# targetboard.net
KiCad netlist of a schematic drawn in EAGLE
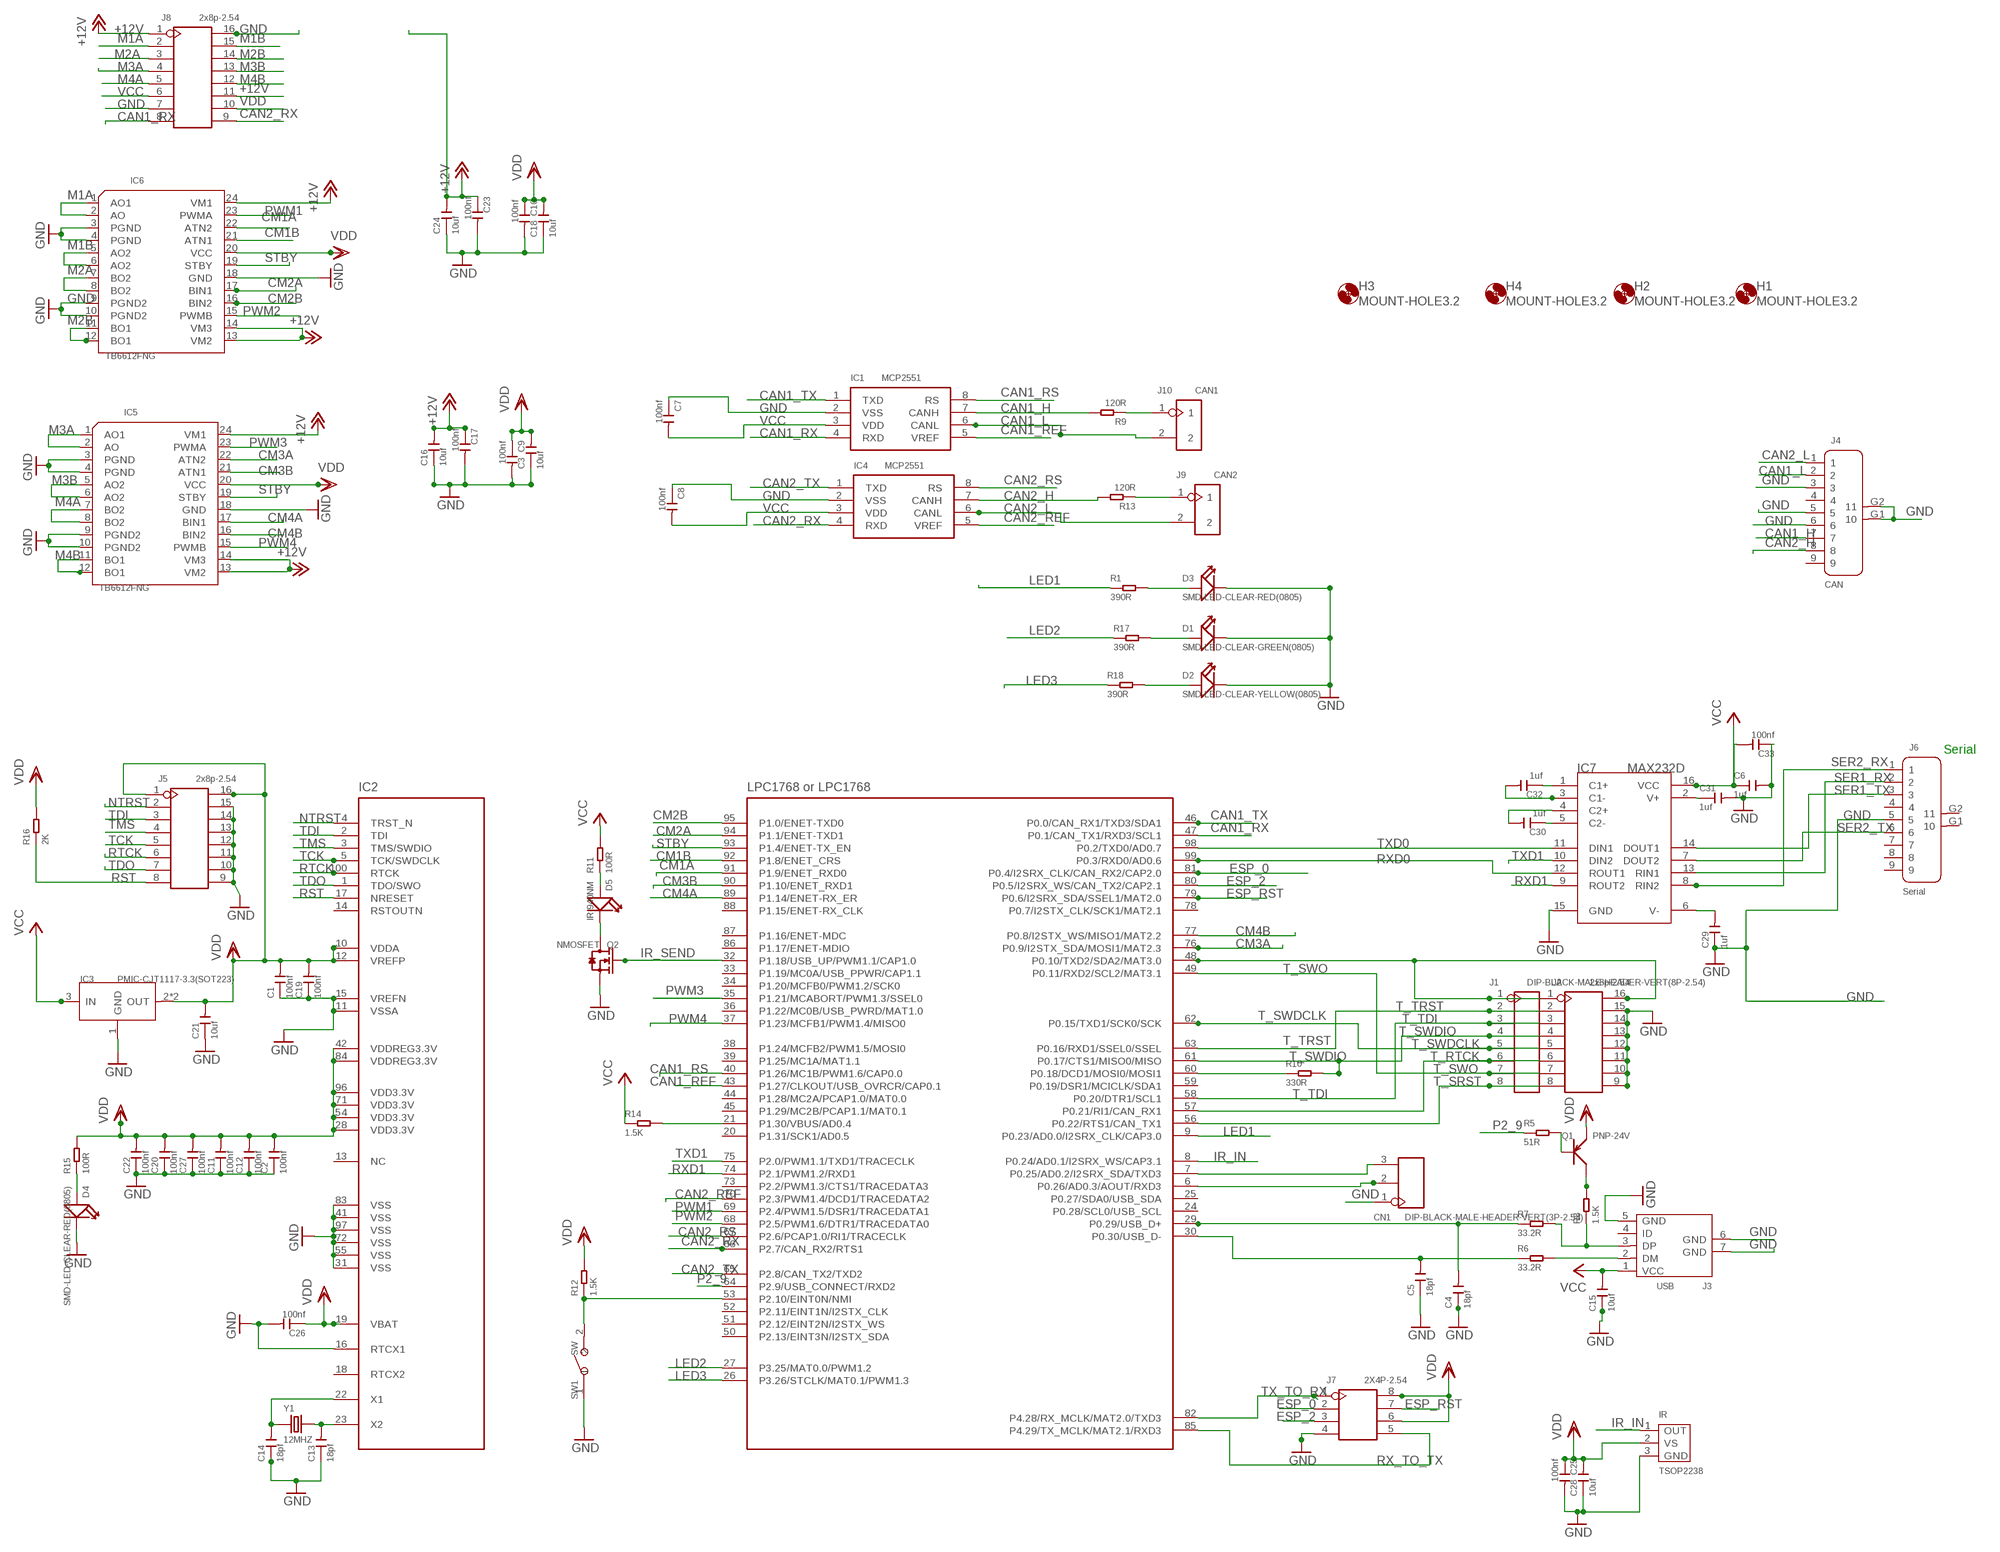
[diagram p0: schematic, sheet 1]

(export (version "E")
  (design (tool "Eeschema 10.0.6"))
  (components
    (comp (ref "C1")
      (value "100nf")
      (footprint "eagle-import:C0805")
      (fields (field (name "MPN") "CC0805KRX7R9BB104"))
      (libsource (lib "eagle-import") (part "CERAMIC-100NF-50V-10%-X7R(0805)"))
    )
    (comp (ref "C2")
      (value "100nf")
      (footprint "eagle-import:C0805")
      (fields (field (name "MPN") "CC0805KRX7R9BB104"))
      (libsource (lib "eagle-import") (part "CERAMIC-100NF-50V-10%-X7R(0805)"))
    )
    (comp (ref "C3")
      (value "10uf")
      (footprint "eagle-import:C0805")
      (fields (field (name "MPN") "CC0805KKX5R8BB106"))
      (libsource (lib "eagle-import") (part "CERAMIC-10UF-25V-10%-X5R(0805)"))
    )
    (comp (ref "C4")
      (value "18pf")
      (footprint "eagle-import:C0805")
      (libsource (lib "eagle-import") (part "CERAMIC-18PF-50V-5%-NPO(0805)"))
    )
    (comp (ref "C5")
      (value "18pf")
      (footprint "eagle-import:C0805")
      (libsource (lib "eagle-import") (part "CERAMIC-18PF-50V-5%-NPO(0805)"))
    )
    (comp (ref "C6")
      (value "1uf")
      (footprint "eagle-import:C0805")
      (fields (field (name "MPN") "CC0805KKX7R8BB105"))
      (libsource (lib "eagle-import") (part "CERAMIC-1UF-25V-10%-X7R(0805)"))
    )
    (comp (ref "C7")
      (value "100nf")
      (footprint "eagle-import:C0805")
      (fields (field (name "MPN") "CC0805KRX7R9BB104"))
      (libsource (lib "eagle-import") (part "CERAMIC-100NF-50V-10%-X7R(0805)"))
    )
    (comp (ref "C8")
      (value "100nf")
      (footprint "eagle-import:C0805")
      (fields (field (name "MPN") "CC0805KRX7R9BB104"))
      (libsource (lib "eagle-import") (part "CERAMIC-100NF-50V-10%-X7R(0805)"))
    )
    (comp (ref "C9")
      (value "100nf")
      (footprint "eagle-import:C0805")
      (fields (field (name "MPN") "CC0805KRX7R9BB104"))
      (libsource (lib "eagle-import") (part "CERAMIC-100NF-50V-10%-X7R(0805)"))
    )
    (comp (ref "C10")
      (value "100nf")
      (footprint "eagle-import:C0805")
      (fields (field (name "MPN") "CC0805KRX7R9BB104"))
      (libsource (lib "eagle-import") (part "CERAMIC-100NF-50V-10%-X7R(0805)"))
    )
    (comp (ref "C11")
      (value "100nf")
      (footprint "eagle-import:C0805")
      (fields (field (name "MPN") "CC0805KRX7R9BB104"))
      (libsource (lib "eagle-import") (part "CERAMIC-100NF-50V-10%-X7R(0805)"))
    )
    (comp (ref "C12")
      (value "100nf")
      (footprint "eagle-import:C0805")
      (fields (field (name "MPN") "CC0805KRX7R9BB104"))
      (libsource (lib "eagle-import") (part "CERAMIC-100NF-50V-10%-X7R(0805)"))
    )
    (comp (ref "C13")
      (value "18pf")
      (footprint "eagle-import:C0805")
      (libsource (lib "eagle-import") (part "CERAMIC-18PF-50V-5%-NPO(0805)"))
    )
    (comp (ref "C14")
      (value "18pf")
      (footprint "eagle-import:C0805")
      (libsource (lib "eagle-import") (part "CERAMIC-18PF-50V-5%-NPO(0805)"))
    )
    (comp (ref "C15")
      (value "10uf")
      (footprint "eagle-import:C0603")
      (fields (field (name "MPN") "CC0603KRX5R6BB106"))
      (libsource (lib "eagle-import") (part "CERAMIC-10UF-10V-10%-X5R(0603)"))
    )
    (comp (ref "C16")
      (value "10uf")
      (footprint "eagle-import:C0805")
      (fields (field (name "MPN") "CC0805KKX5R8BB106"))
      (libsource (lib "eagle-import") (part "CERAMIC-10UF-25V-10%-X5R(0805)"))
    )
    (comp (ref "C17")
      (value "100nf")
      (footprint "eagle-import:C0805")
      (fields (field (name "MPN") "CC0805KRX7R9BB104"))
      (libsource (lib "eagle-import") (part "CERAMIC-100NF-50V-10%-X7R(0805)"))
    )
    (comp (ref "C18")
      (value "10uf")
      (footprint "eagle-import:C0805")
      (fields (field (name "MPN") "CC0805KKX5R8BB106"))
      (libsource (lib "eagle-import") (part "CERAMIC-10UF-25V-10%-X5R(0805)"))
    )
    (comp (ref "C19")
      (value "100nf")
      (footprint "eagle-import:C0805")
      (fields (field (name "MPN") "CC0805KRX7R9BB104"))
      (libsource (lib "eagle-import") (part "CERAMIC-100NF-50V-10%-X7R(0805)"))
    )
    (comp (ref "C20")
      (value "100nf")
      (footprint "eagle-import:C0805")
      (fields (field (name "MPN") "CC0805KRX7R9BB104"))
      (libsource (lib "eagle-import") (part "CERAMIC-100NF-50V-10%-X7R(0805)"))
    )
    (comp (ref "C21")
      (value "10uf")
      (footprint "eagle-import:C0805")
      (fields (field (name "MPN") "CC0805KKX5R8BB106"))
      (libsource (lib "eagle-import") (part "CERAMIC-10UF-25V-10%-X5R(0805)"))
    )
    (comp (ref "C22")
      (value "100nf")
      (footprint "eagle-import:C0805")
      (fields (field (name "MPN") "CC0805KRX7R9BB104"))
      (libsource (lib "eagle-import") (part "CERAMIC-100NF-50V-10%-X7R(0805)"))
    )
    (comp (ref "C23")
      (value "100nf")
      (footprint "eagle-import:C0805")
      (fields (field (name "MPN") "CC0805KRX7R9BB104"))
      (libsource (lib "eagle-import") (part "CERAMIC-100NF-50V-10%-X7R(0805)"))
    )
    (comp (ref "C24")
      (value "10uf")
      (footprint "eagle-import:C0805")
      (fields (field (name "MPN") "CC0805KKX5R8BB106"))
      (libsource (lib "eagle-import") (part "CERAMIC-10UF-25V-10%-X5R(0805)"))
    )
    (comp (ref "C25")
      (value "100nf")
      (footprint "eagle-import:C0805")
      (fields (field (name "MPN") "CC0805KRX7R9BB104"))
      (libsource (lib "eagle-import") (part "CERAMIC-100NF-50V-10%-X7R(0805)"))
    )
    (comp (ref "C26")
      (value "100nf")
      (footprint "eagle-import:C0805")
      (fields (field (name "MPN") "CC0805KRX7R9BB104"))
      (libsource (lib "eagle-import") (part "CERAMIC-100NF-50V-10%-X7R(0805)"))
    )
    (comp (ref "C27")
      (value "100nf")
      (footprint "eagle-import:C0805")
      (fields (field (name "MPN") "CC0805KRX7R9BB104"))
      (libsource (lib "eagle-import") (part "CERAMIC-100NF-50V-10%-X7R(0805)"))
    )
    (comp (ref "C28")
      (value "10uf")
      (footprint "eagle-import:C0805")
      (fields (field (name "MPN") "CC0805KKX5R8BB106"))
      (libsource (lib "eagle-import") (part "CERAMIC-10UF-25V-10%-X5R(0805)"))
    )
    (comp (ref "C29")
      (value "1uf")
      (footprint "eagle-import:C0805")
      (fields (field (name "MPN") "CC0805KKX7R8BB105"))
      (libsource (lib "eagle-import") (part "CERAMIC-1UF-25V-10%-X7R(0805)"))
    )
    (comp (ref "C30")
      (value "1uf")
      (footprint "eagle-import:C0805")
      (fields (field (name "MPN") "CC0805KKX7R8BB105"))
      (libsource (lib "eagle-import") (part "CERAMIC-1UF-25V-10%-X7R(0805)"))
    )
    (comp (ref "C31")
      (value "1uf")
      (footprint "eagle-import:C0805")
      (fields (field (name "MPN") "CC0805KKX7R8BB105"))
      (libsource (lib "eagle-import") (part "CERAMIC-1UF-25V-10%-X7R(0805)"))
    )
    (comp (ref "C32")
      (value "1uf")
      (footprint "eagle-import:C0805")
      (fields (field (name "MPN") "CC0805KKX7R8BB105"))
      (libsource (lib "eagle-import") (part "CERAMIC-1UF-25V-10%-X7R(0805)"))
    )
    (comp (ref "C33")
      (value "100nf")
      (footprint "eagle-import:C0805")
      (fields (field (name "MPN") "CC0805KRX7R9BB104"))
      (libsource (lib "eagle-import") (part "CERAMIC-100NF-50V-10%-X7R(0805)"))
    )
    (comp (ref "CN1")
      (value "DIP-BLACK-MALE-HEADER-VERT(3P-2.54)")
      (footprint "eagle-import:H3-2.54")
      (libsource (lib "eagle-import") (part "DIP-BLACK-MALE-HEADER-VERT(3P-2.54)"))
    )
    (comp (ref "D1")
      (value "SMD-LED-CLEAR-GREEN(0805)")
      (footprint "eagle-import:LED-0805")
      (fields (field (name "MPN") "17-215SYGC/S530-E2/TR8"))
      (libsource (lib "eagle-import") (part "SMD-LED-CLEAR-GREEN(0805)"))
    )
    (comp (ref "D2")
      (value "SMD-LED-CLEAR-YELLOW(0805)")
      (footprint "eagle-import:LED-0805")
      (fields (field (name "MPN") "17-215UYC/S530-A3/TR8"))
      (libsource (lib "eagle-import") (part "SMD-LED-CLEAR-YELLOW(0805)"))
    )
    (comp (ref "D3")
      (value "SMD-LED-CLEAR-RED(0805)")
      (footprint "eagle-import:LED-0805")
      (fields (field (name "MPN") "17-215SURC/S530-A2/TR8"))
      (libsource (lib "eagle-import") (part "SMD-LED-CLEAR-RED(0805)"))
    )
    (comp (ref "D4")
      (value "SMD-LED-CLEAR-RED(0805)")
      (footprint "eagle-import:LED-0805")
      (fields (field (name "MPN") "17-215SURC/S530-A2/TR8"))
      (libsource (lib "eagle-import") (part "SMD-LED-CLEAR-RED(0805)"))
    )
    (comp (ref "D5")
      (value "IR 940NM")
      (footprint "eagle-import:LED2-2.54-D5.0MM")
      (fields (field (name "MPN") "IR523B-W60W1"))
      (libsource (lib "eagle-import") (part "DIP-IR-LED-940NM(2P-D5MM)"))
    )
    (comp (ref "H1")
      (value "MOUNT-HOLE3.2")
      (footprint "eagle-import:3,2")
      (libsource (lib "eagle-import") (part "MOUNT-HOLE3.2"))
    )
    (comp (ref "H2")
      (value "MOUNT-HOLE3.2")
      (footprint "eagle-import:3,2")
      (libsource (lib "eagle-import") (part "MOUNT-HOLE3.2"))
    )
    (comp (ref "H3")
      (value "MOUNT-HOLE3.2")
      (footprint "eagle-import:3,2")
      (libsource (lib "eagle-import") (part "MOUNT-HOLE3.2"))
    )
    (comp (ref "H4")
      (value "MOUNT-HOLE3.2")
      (footprint "eagle-import:3,2")
      (libsource (lib "eagle-import") (part "MOUNT-HOLE3.2"))
    )
    (comp (ref "IC1")
      (value "MCP2551")
      (footprint "eagle-import:SOIC8-1.27-5X4MM")
      (fields (field (name "MPN") "MCP2551-I/SN"))
      (libsource (lib "eagle-import") (part "INTERFACE-MCP2551-I/SN(SOIC8)"))
    )
    (comp (ref "IC2")
      (value "LPC1768 or LPC1768")
      (footprint "eagle-import:LQFP100-0.5-13.8X13.8MM")
      (fields (field (name "MPN") "LPC1768FBD100"))
      (libsource (lib "eagle-import") (part "MCU_LPC1768FBD100(LQFP100)"))
    )
    (comp (ref "IC3")
      (value "PMIC-CJT1117-3.3(SOT223)")
      (footprint "eagle-import:SOT-223")
      (fields (field (name "MPN") "CJT1117-3.3"))
      (libsource (lib "eagle-import") (part "PMIC-CJT1117-3.3(SOT223)"))
    )
    (comp (ref "IC4")
      (value "MCP2551")
      (footprint "eagle-import:SOIC8-1.27-5X4MM")
      (fields (field (name "MPN") "MCP2551-I/SN"))
      (libsource (lib "eagle-import") (part "INTERFACE-MCP2551-I/SN(SOIC8)"))
    )
    (comp (ref "IC5")
      (value "TB6612FNG")
      (footprint "eagle-import:SSOP24-0.65-8.9X5.3MM")
      (fields (field (name "MPN") "TB6612FNG-O/C8/EL"))
      (libsource (lib "eagle-import") (part "DRIVER-TB6612FNG-O/C8/EL(SSOP24)"))
    )
    (comp (ref "IC6")
      (value "TB6612FNG")
      (footprint "eagle-import:SSOP24-0.65-8.9X5.3MM")
      (fields (field (name "MPN") "TB6612FNG-O/C8/EL"))
      (libsource (lib "eagle-import") (part "DRIVER-TB6612FNG-O/C8/EL(SSOP24)"))
    )
    (comp (ref "IC7")
      (value "MAX232D")
      (footprint "eagle-import:SOIC16-1.27-10X3.9MM")
      (libsource (lib "eagle-import") (part "RECEIVER-MAX232D(SOIC16)"))
    )
    (comp (ref "IR")
      (value "TSOP2238")
      (footprint "eagle-import:SNR3-2.54-6.95X6.0X5.6MM")
      (libsource (lib "eagle-import") (part "OPTICAL-TSOP2238"))
    )
    (comp (ref "J1")
      (value "DIP-BLACK-MALE-HEADER-VERT(8P-2.54)")
      (footprint "eagle-import:H8-2.54")
      (fields (field (name "MPN") "P125-1108A1BS116A1"))
      (libsource (lib "eagle-import") (part "DIP-BLACK-MALE-HEADER-VERT(8P-2.54)"))
    )
    (comp (ref "J2")
      (value "2x8p-2.54")
      (footprint "eagle-import:H2X8-2.54")
      (fields (field (name "MPN") "P125-1216A0AS116A1"))
      (libsource (lib "eagle-import") (part "DIP-BLACK-MALE-HEADER-VERT(2X8P-2.54)"))
    )
    (comp (ref "J3")
      (value "USB")
      (footprint "eagle-import:MICRO-USB5+2P-SMD-0.65")
      (fields (field (name "MPN") "ST-USB-001L"))
      (libsource (lib "eagle-import") (part "MICRO-USB-SMD-TYPE-AB-R/A(ST-USB-001L)"))
    )
    (comp (ref "J4")
      (value "CAN")
      (footprint "eagle-import:DSUB9+2P-2.77-90D-MALE")
      (libsource (lib "eagle-import") (part "DIP-MALE-DB9-CONNECTOR"))
    )
    (comp (ref "J5")
      (value "2x8p-2.54")
      (footprint "eagle-import:H2X8-2.54")
      (fields (field (name "MPN") "P125-1216A0AS116A1"))
      (libsource (lib "eagle-import") (part "DIP-BLACK-MALE-HEADER-VERT(2X8P-2.54)"))
    )
    (comp (ref "J6")
      (value "Serial")
      (footprint "eagle-import:DSUB9+2P-2.77-90D-MALE")
      (libsource (lib "eagle-import") (part "DIP-MALE-DB9-CONNECTOR"))
    )
    (comp (ref "J7")
      (value "2X4P-2.54")
      (footprint "eagle-import:H2X4-2.54")
      (libsource (lib "eagle-import") (part "DIP-BLACK-FEMALE-HEADER(2X4P-2.54)"))
    )
    (comp (ref "J8")
      (value "2x8p-2.54")
      (footprint "eagle-import:H2X8-2.54")
      (fields (field (name "MPN") "P125-1216A0AS116A1"))
      (libsource (lib "eagle-import") (part "DIP-BLACK-MALE-HEADER-VERT(2X8P-2.54)"))
    )
    (comp (ref "J9")
      (value "CAN2")
      (footprint "eagle-import:H2-2.54")
      (fields (field (name "MPN") "P125-1102A0BS116A3"))
      (libsource (lib "eagle-import") (part "DIP-WHITE-MALE-HEADER-VERT(2P-2.54)"))
    )
    (comp (ref "J10")
      (value "CAN1")
      (footprint "eagle-import:H2-2.54")
      (fields (field (name "MPN") "P125-1102A0BS116A3"))
      (libsource (lib "eagle-import") (part "DIP-WHITE-MALE-HEADER-VERT(2P-2.54)"))
    )
    (comp (ref "Q1")
      (value "PNP-24V")
      (footprint "eagle-import:SOT-23")
      (fields (field (name "MPN") "S8550"))
      (libsource (lib "eagle-import") (part "SMD-TRANSISTORS-PNP-25V-500MA(SOT-23)"))
    )
    (comp (ref "Q2")
      (value "NMOSFET")
      (footprint "eagle-import:SOT-23")
      (fields (field (name "MPN") "2N7002,215"))
      (libsource (lib "eagle-import") (part "SMD-MOSFET-N-CH-60V-300MA-LOGIC-LEVEL-FET(SOT-23)"))
    )
    (comp (ref "R1")
      (value "390R")
      (footprint "eagle-import:R0805")
      (fields (field (name "MPN") "RC0805JR-07390RL"))
      (libsource (lib "eagle-import") (part "SMD-RES-390R-5%-1/8W(0805)"))
    )
    (comp (ref "R5")
      (value "51R")
      (footprint "eagle-import:R0603")
      (fields (field (name "MPN") "RC0603FR-0751RL"))
      (libsource (lib "eagle-import") (part "SMD-RES-51R-1%-1/10W(0603)"))
    )
    (comp (ref "R6")
      (value "33.2R")
      (footprint "eagle-import:R0603")
      (fields (field (name "MPN") "RC0603FR-0733R2L"))
      (libsource (lib "eagle-import") (part "SMD-RES-33.2R-1%-1/10W(0603)"))
    )
    (comp (ref "R7")
      (value "33.2R")
      (footprint "eagle-import:R0603")
      (fields (field (name "MPN") "RC0603FR-0733R2L"))
      (libsource (lib "eagle-import") (part "SMD-RES-33.2R-1%-1/10W(0603)"))
    )
    (comp (ref "R8")
      (value "1.5K")
      (footprint "eagle-import:R0805")
      (fields (field (name "MPN") "RC0805FR-071K5L"))
      (libsource (lib "eagle-import") (part "SMD-RES-1.5K-1%-1/8W(0805)"))
    )
    (comp (ref "R9")
      (value "120R")
      (footprint "eagle-import:R0805")
      (fields (field (name "MPN") "RC0805JR-07120RL"))
      (libsource (lib "eagle-import") (part "SMD-RES-120R-5%-1/8W(0805)"))
    )
    (comp (ref "R10")
      (value "330R")
      (footprint "eagle-import:R0603")
      (fields (field (name "MPN") "RC0603FR-07330RL"))
      (libsource (lib "eagle-import") (part "SMD-RES-330R-1%-1/10W(0603)"))
    )
    (comp (ref "R11")
      (value "100R")
      (footprint "eagle-import:R0805")
      (fields (field (name "MPN") "RC0805JR-07100RL"))
      (libsource (lib "eagle-import") (part "SMD-RES-100R-5%-1/8W(0805)"))
    )
    (comp (ref "R12")
      (value "1.5K")
      (footprint "eagle-import:R0805")
      (fields (field (name "MPN") "RC0805FR-071K5L"))
      (libsource (lib "eagle-import") (part "SMD-RES-1.5K-1%-1/8W(0805)"))
    )
    (comp (ref "R13")
      (value "120R")
      (footprint "eagle-import:R0805")
      (fields (field (name "MPN") "RC0805JR-07120RL"))
      (libsource (lib "eagle-import") (part "SMD-RES-120R-5%-1/8W(0805)"))
    )
    (comp (ref "R14")
      (value "1.5K")
      (footprint "eagle-import:R0805")
      (fields (field (name "MPN") "RC0805FR-071K5L"))
      (libsource (lib "eagle-import") (part "SMD-RES-1.5K-1%-1/8W(0805)"))
    )
    (comp (ref "R15")
      (value "100R")
      (footprint "eagle-import:R0805")
      (fields (field (name "MPN") "RC0805JR-07100RL"))
      (libsource (lib "eagle-import") (part "SMD-RES-100R-5%-1/8W(0805)"))
    )
    (comp (ref "R16")
      (value "2K")
      (footprint "eagle-import:R0805")
      (fields (field (name "MPN") "RC0805JR-072KL"))
      (libsource (lib "eagle-import") (part "SMD-RES-2K-5%-1/8W(0805)"))
    )
    (comp (ref "R17")
      (value "390R")
      (footprint "eagle-import:R0805")
      (fields (field (name "MPN") "RC0805JR-07390RL"))
      (libsource (lib "eagle-import") (part "SMD-RES-390R-5%-1/8W(0805)"))
    )
    (comp (ref "R18")
      (value "390R")
      (footprint "eagle-import:R0805")
      (fields (field (name "MPN") "RC0805JR-07390RL"))
      (libsource (lib "eagle-import") (part "SMD-RES-390R-5%-1/8W(0805)"))
    )
    (comp (ref "SW1")
      (value "SW")
      (footprint "eagle-import:SW2-2.6-3.0X2.5X1.2+0.4MM")
      (libsource (lib "eagle-import") (part "SMD-BUTTON(2P-3.0X2.5X1.2+0.4MM)-B3U-1000P-2P-SMD"))
    )
    (comp (ref "Y1")
      (value "12MHZ")
      (footprint "eagle-import:X2-SMD-5.0X3.2X1.3MM")
      (fields (field (name "MPN") "5032/2P"))
      (libsource (lib "eagle-import") (part "SMD-CRYSTAL-12MHZ-20PF-20PPM-40R(2P-5.0X3.2MM)"))
    )
  )
  (nets
    (net (code "1") (name "+12V") (class "Default")
      (node (ref "C16") (pin "2") (pinfunction "2_2") (pintype "passive"))
      (node (ref "C17") (pin "1") (pinfunction "1_1") (pintype "passive"))
      (node (ref "C23") (pin "1") (pinfunction "1_1") (pintype "passive"))
      (node (ref "C24") (pin "2") (pinfunction "2_2") (pintype "passive"))
      (node (ref "IC5") (pin "13") (pinfunction "VM2_13") (pintype "bidirectional"))
      (node (ref "IC5") (pin "14") (pinfunction "VM3_14") (pintype "bidirectional"))
      (node (ref "IC5") (pin "24") (pinfunction "VM1_24") (pintype "bidirectional"))
      (node (ref "IC6") (pin "13") (pinfunction "VM2_13") (pintype "bidirectional"))
      (node (ref "IC6") (pin "14") (pinfunction "VM3_14") (pintype "bidirectional"))
      (node (ref "IC6") (pin "24") (pinfunction "VM1_24") (pintype "bidirectional"))
      (node (ref "J8") (pin "1") (pinfunction "1_1") (pintype "bidirectional"))
      (node (ref "J8") (pin "11") (pinfunction "11_11") (pintype "bidirectional"))
    )
    (net (code "2") (name "/CAN1_H") (class "Default")
      (node (ref "IC1") (pin "7") (pinfunction "CANH_7") (pintype "bidirectional"))
      (node (ref "J4") (pin "7") (pinfunction "7_7") (pintype "bidirectional"))
      (node (ref "R9") (pin "2") (pinfunction "2_2") (pintype "passive"))
    )
    (net (code "3") (name "/CAN1_L") (class "Default")
      (node (ref "IC1") (pin "6") (pinfunction "CANL_6") (pintype "bidirectional"))
      (node (ref "J10") (pin "2") (pinfunction "2_2") (pintype "bidirectional"))
      (node (ref "J4") (pin "2") (pinfunction "2_2") (pintype "bidirectional"))
    )
    (net (code "4") (name "/CAN1_REF") (class "Default")
      (node (ref "IC1") (pin "5") (pinfunction "VREF_5") (pintype "bidirectional"))
      (node (ref "IC2") (pin "43") (pinfunction "P1.27/CLKOUT/USB_OVRCR/CAP0.1_43") (pintype "bidirectional"))
    )
    (net (code "5") (name "/CAN1_RS") (class "Default")
      (node (ref "IC1") (pin "8") (pinfunction "RS_8") (pintype "bidirectional"))
      (node (ref "IC2") (pin "40") (pinfunction "P1.26/MC1B/PWM1.6/CAP0.0_40") (pintype "bidirectional"))
    )
    (net (code "6") (name "/CAN1_RX") (class "Default")
      (node (ref "IC1") (pin "4") (pinfunction "RXD_4") (pintype "bidirectional"))
      (node (ref "IC2") (pin "47") (pinfunction "P0.1/CAN_TX1/RXD3/SCL1_47") (pintype "bidirectional"))
      (node (ref "J8") (pin "8") (pinfunction "8_8") (pintype "bidirectional"))
    )
    (net (code "7") (name "/CAN1_TX") (class "Default")
      (node (ref "IC1") (pin "1") (pinfunction "TXD_1") (pintype "bidirectional"))
      (node (ref "IC2") (pin "46") (pinfunction "P0.0/CAN_RX1/TXD3/SDA1_46") (pintype "bidirectional"))
    )
    (net (code "8") (name "/CAN2_H") (class "Default")
      (node (ref "IC4") (pin "7") (pinfunction "CANH_7") (pintype "bidirectional"))
      (node (ref "J4") (pin "8") (pinfunction "8_8") (pintype "bidirectional"))
      (node (ref "R13") (pin "2") (pinfunction "2_2") (pintype "passive"))
    )
    (net (code "9") (name "/CAN2_L") (class "Default")
      (node (ref "IC4") (pin "6") (pinfunction "CANL_6") (pintype "bidirectional"))
      (node (ref "J4") (pin "1") (pinfunction "1_1") (pintype "bidirectional"))
      (node (ref "J9") (pin "2") (pinfunction "2_2") (pintype "bidirectional"))
    )
    (net (code "10") (name "/CAN2_REF") (class "Default")
      (node (ref "IC2") (pin "70") (pinfunction "P2.3/PWM1.4/DCD1/TRACEDATA2_70") (pintype "bidirectional"))
      (node (ref "IC4") (pin "5") (pinfunction "VREF_5") (pintype "bidirectional"))
    )
    (net (code "11") (name "/CAN2_RS") (class "Default")
      (node (ref "IC2") (pin "67") (pinfunction "P2.6/PCAP1.0/RI1/TRACECLK_67") (pintype "bidirectional"))
      (node (ref "IC4") (pin "8") (pinfunction "RS_8") (pintype "bidirectional"))
    )
    (net (code "12") (name "/CAN2_RX") (class "Default")
      (node (ref "IC2") (pin "66") (pinfunction "P2.7/CAN_RX2/RTS1_66") (pintype "bidirectional"))
      (node (ref "IC4") (pin "4") (pinfunction "RXD_4") (pintype "bidirectional"))
      (node (ref "J8") (pin "9") (pinfunction "9_9") (pintype "bidirectional"))
    )
    (net (code "13") (name "/CAN2_TX") (class "Default")
      (node (ref "IC2") (pin "65") (pinfunction "P2.8/CAN_TX2/TXD2_65") (pintype "bidirectional"))
      (node (ref "IC4") (pin "1") (pinfunction "TXD_1") (pintype "bidirectional"))
    )
    (net (code "14") (name "/CM1A") (class "Default")
      (node (ref "IC2") (pin "91") (pinfunction "P1.9/ENET_RXD0_91") (pintype "bidirectional"))
      (node (ref "IC6") (pin "22") (pinfunction "ATN2_22") (pintype "bidirectional"))
    )
    (net (code "15") (name "/CM1B") (class "Default")
      (node (ref "IC2") (pin "92") (pinfunction "P1.8/ENET_CRS_92") (pintype "bidirectional"))
      (node (ref "IC6") (pin "21") (pinfunction "ATN1_21") (pintype "bidirectional"))
    )
    (net (code "16") (name "/CM2A") (class "Default")
      (node (ref "IC2") (pin "94") (pinfunction "P1.1/ENET-TXD1_94") (pintype "bidirectional"))
      (node (ref "IC6") (pin "17") (pinfunction "BIN1_17") (pintype "bidirectional"))
    )
    (net (code "17") (name "/CM2B") (class "Default")
      (node (ref "IC2") (pin "95") (pinfunction "P1.0/ENET-TXD0_95") (pintype "bidirectional"))
      (node (ref "IC6") (pin "16") (pinfunction "BIN2_16") (pintype "bidirectional"))
    )
    (net (code "18") (name "/CM3A") (class "Default")
      (node (ref "IC2") (pin "76") (pinfunction "P0.9/I2STX_SDA/MOSI1/MAT2.3_76") (pintype "bidirectional"))
      (node (ref "IC5") (pin "22") (pinfunction "ATN2_22") (pintype "bidirectional"))
    )
    (net (code "19") (name "/CM3B") (class "Default")
      (node (ref "IC2") (pin "90") (pinfunction "P1.10/ENET_RXD1_90") (pintype "bidirectional"))
      (node (ref "IC5") (pin "21") (pinfunction "ATN1_21") (pintype "bidirectional"))
    )
    (net (code "20") (name "/CM4A") (class "Default")
      (node (ref "IC2") (pin "89") (pinfunction "P1.14/ENET-RX_ER_89") (pintype "bidirectional"))
      (node (ref "IC5") (pin "17") (pinfunction "BIN1_17") (pintype "bidirectional"))
    )
    (net (code "21") (name "/CM4B") (class "Default")
      (node (ref "IC2") (pin "77") (pinfunction "P0.8/I2STX_WS/MISO1/MAT2.2_77") (pintype "bidirectional"))
      (node (ref "IC5") (pin "16") (pinfunction "BIN2_16") (pintype "bidirectional"))
    )
    (net (code "22") (name "/ESP_0") (class "Default")
      (node (ref "IC2") (pin "81") (pinfunction "P0.4/I2SRX_CLK/CAN_RX2/CAP2.0_81") (pintype "bidirectional"))
      (node (ref "J7") (pin "2") (pinfunction "2_2") (pintype "bidirectional"))
    )
    (net (code "23") (name "/ESP_2") (class "Default")
      (node (ref "IC2") (pin "80") (pinfunction "P0.5/I2SRX_WS/CAN_TX2/CAP2.1_80") (pintype "bidirectional"))
      (node (ref "J7") (pin "3") (pinfunction "3_3") (pintype "bidirectional"))
    )
    (net (code "24") (name "/ESP_RST") (class "Default")
      (node (ref "IC2") (pin "79") (pinfunction "P0.6/I2SRX_SDA/SSEL1/MAT2.0_79") (pintype "bidirectional"))
      (node (ref "J7") (pin "7") (pinfunction "7_7") (pintype "bidirectional"))
    )
    (net (code "25") (name "/IR_IN") (class "Default")
      (node (ref "IC2") (pin "8") (pinfunction "P0.24/AD0.1/I2SRX_WS/CAP3.1_8") (pintype "bidirectional"))
      (node (ref "IR") (pin "1") (pinfunction "OUT_1") (pintype "bidirectional"))
    )
    (net (code "26") (name "/IR_SEND") (class "Default")
      (node (ref "IC2") (pin "32") (pinfunction "P1.18/USB_UP/PWM1.1/CAP1.0_32") (pintype "bidirectional"))
      (node (ref "Q2") (pin "1") (pinfunction "G_1") (pintype "passive"))
    )
    (net (code "27") (name "/LED1") (class "Default")
      (node (ref "IC2") (pin "9") (pinfunction "P0.23/AD0.0/I2SRX_CLK/CAP3.0_9") (pintype "bidirectional"))
      (node (ref "R1") (pin "1") (pinfunction "1_1") (pintype "passive"))
    )
    (net (code "28") (name "/LED2") (class "Default")
      (node (ref "IC2") (pin "27") (pinfunction "P3.25/MAT0.0/PWM1.2_27") (pintype "bidirectional"))
      (node (ref "R17") (pin "1") (pinfunction "1_1") (pintype "passive"))
    )
    (net (code "29") (name "/LED3") (class "Default")
      (node (ref "IC2") (pin "26") (pinfunction "P3.26/STCLK/MAT0.1/PWM1.3_26") (pintype "bidirectional"))
      (node (ref "R18") (pin "1") (pinfunction "1_1") (pintype "passive"))
    )
    (net (code "30") (name "/M1A") (class "Default")
      (node (ref "IC6") (pin "1") (pinfunction "AO1_1") (pintype "bidirectional"))
      (node (ref "IC6") (pin "2") (pinfunction "AO_2") (pintype "bidirectional"))
      (node (ref "J8") (pin "2") (pinfunction "2_2") (pintype "bidirectional"))
    )
    (net (code "31") (name "/M1B") (class "Default")
      (node (ref "IC6") (pin "5") (pinfunction "AO2_5") (pintype "bidirectional"))
      (node (ref "IC6") (pin "6") (pinfunction "AO2_6") (pintype "bidirectional"))
      (node (ref "J8") (pin "15") (pinfunction "15_15") (pintype "bidirectional"))
    )
    (net (code "32") (name "/M2A") (class "Default")
      (node (ref "IC6") (pin "7") (pinfunction "BO2_7") (pintype "bidirectional"))
      (node (ref "IC6") (pin "8") (pinfunction "BO2_8") (pintype "bidirectional"))
      (node (ref "J8") (pin "3") (pinfunction "3_3") (pintype "bidirectional"))
    )
    (net (code "33") (name "/M2B") (class "Default")
      (node (ref "IC6") (pin "11") (pinfunction "BO1_11") (pintype "bidirectional"))
      (node (ref "IC6") (pin "12") (pinfunction "BO1_12") (pintype "bidirectional"))
      (node (ref "J8") (pin "14") (pinfunction "14_14") (pintype "bidirectional"))
    )
    (net (code "34") (name "/M3A") (class "Default")
      (node (ref "IC5") (pin "1") (pinfunction "AO1_1") (pintype "bidirectional"))
      (node (ref "IC5") (pin "2") (pinfunction "AO_2") (pintype "bidirectional"))
      (node (ref "J8") (pin "4") (pinfunction "4_4") (pintype "bidirectional"))
    )
    (net (code "35") (name "/M3B") (class "Default")
      (node (ref "IC5") (pin "5") (pinfunction "AO2_5") (pintype "bidirectional"))
      (node (ref "IC5") (pin "6") (pinfunction "AO2_6") (pintype "bidirectional"))
      (node (ref "J8") (pin "13") (pinfunction "13_13") (pintype "bidirectional"))
    )
    (net (code "36") (name "/M4A") (class "Default")
      (node (ref "IC5") (pin "7") (pinfunction "BO2_7") (pintype "bidirectional"))
      (node (ref "IC5") (pin "8") (pinfunction "BO2_8") (pintype "bidirectional"))
      (node (ref "J8") (pin "5") (pinfunction "5_5") (pintype "bidirectional"))
    )
    (net (code "37") (name "/M4B") (class "Default")
      (node (ref "IC5") (pin "11") (pinfunction "BO1_11") (pintype "bidirectional"))
      (node (ref "IC5") (pin "12") (pinfunction "BO1_12") (pintype "bidirectional"))
      (node (ref "J8") (pin "12") (pinfunction "12_12") (pintype "bidirectional"))
    )
    (net (code "38") (name "/NTRST") (class "Default")
      (node (ref "IC2") (pin "4") (pinfunction "TRST_N_4") (pintype "bidirectional"))
      (node (ref "J5") (pin "2") (pinfunction "2_2") (pintype "bidirectional"))
    )
    (net (code "39") (name "/P2_9") (class "Default")
      (node (ref "IC2") (pin "64") (pinfunction "P2.9/USB_CONNECT/RXD2_64") (pintype "bidirectional"))
      (node (ref "R5") (pin "1") (pinfunction "1_1") (pintype "passive"))
    )
    (net (code "40") (name "/PWM1") (class "Default")
      (node (ref "IC2") (pin "69") (pinfunction "P2.4/PWM1.5/DSR1/TRACEDATA1_69") (pintype "bidirectional"))
      (node (ref "IC6") (pin "23") (pinfunction "PWMA_23") (pintype "bidirectional"))
    )
    (net (code "41") (name "/PWM2") (class "Default")
      (node (ref "IC2") (pin "68") (pinfunction "P2.5/PWM1.6/DTR1/TRACEDATA0_68") (pintype "bidirectional"))
      (node (ref "IC6") (pin "15") (pinfunction "PWMB_15") (pintype "bidirectional"))
    )
    (net (code "42") (name "/PWM3") (class "Default")
      (node (ref "IC2") (pin "35") (pinfunction "P1.21/MCABORT/PWM1.3/SSEL0_35") (pintype "bidirectional"))
      (node (ref "IC5") (pin "23") (pinfunction "PWMA_23") (pintype "bidirectional"))
    )
    (net (code "43") (name "/PWM4") (class "Default")
      (node (ref "IC2") (pin "37") (pinfunction "P1.23/MCFB1/PWM1.4/MISO0_37") (pintype "bidirectional"))
      (node (ref "IC5") (pin "15") (pinfunction "PWMB_15") (pintype "bidirectional"))
    )
    (net (code "44") (name "/RST") (class "Default")
      (node (ref "IC2") (pin "17") (pinfunction "NRESET_17") (pintype "bidirectional"))
      (node (ref "J5") (pin "8") (pinfunction "8_8") (pintype "bidirectional"))
      (node (ref "R16") (pin "1") (pinfunction "1_1") (pintype "passive"))
    )
    (net (code "45") (name "/RTCK") (class "Default")
      (node (ref "IC2") (pin "100") (pinfunction "RTCK_100") (pintype "bidirectional"))
      (node (ref "J5") (pin "6") (pinfunction "6_6") (pintype "bidirectional"))
    )
    (net (code "46") (name "/RXD0") (class "Default")
      (node (ref "IC2") (pin "99") (pinfunction "P0.3/RXD0/AD0.6_99") (pintype "bidirectional"))
      (node (ref "IC7") (pin "12") (pinfunction "ROUT1_12") (pintype "bidirectional"))
    )
    (net (code "47") (name "/RXD1") (class "Default")
      (node (ref "IC2") (pin "74") (pinfunction "P2.1/PWM1.2/RXD1_74") (pintype "bidirectional"))
      (node (ref "IC7") (pin "9") (pinfunction "ROUT2_9") (pintype "bidirectional"))
    )
    (net (code "48") (name "/RX_TO_TX") (class "Default")
      (node (ref "IC2") (pin "85") (pinfunction "P4.29/TX_MCLK/MAT2.1/RXD3_85") (pintype "bidirectional"))
      (node (ref "J7") (pin "5") (pinfunction "5_5") (pintype "bidirectional"))
    )
    (net (code "49") (name "/SER1_RX") (class "Default")
      (node (ref "IC7") (pin "13") (pinfunction "RIN1_13") (pintype "bidirectional"))
      (node (ref "J6") (pin "2") (pinfunction "2_2") (pintype "bidirectional"))
    )
    (net (code "50") (name "/SER1_TX") (class "Default")
      (node (ref "IC7") (pin "14") (pinfunction "DOUT1_14") (pintype "bidirectional"))
      (node (ref "J6") (pin "3") (pinfunction "3_3") (pintype "bidirectional"))
    )
    (net (code "51") (name "/SER2_RX") (class "Default")
      (node (ref "IC7") (pin "8") (pinfunction "RIN2_8") (pintype "bidirectional"))
      (node (ref "J6") (pin "1") (pinfunction "1_1") (pintype "bidirectional"))
    )
    (net (code "52") (name "/SER2_TX") (class "Default")
      (node (ref "IC7") (pin "7") (pinfunction "DOUT2_7") (pintype "bidirectional"))
      (node (ref "J6") (pin "6") (pinfunction "6_6") (pintype "bidirectional"))
    )
    (net (code "53") (name "/STBY") (class "Default")
      (node (ref "IC2") (pin "93") (pinfunction "P1.4/ENET-TX_EN_93") (pintype "bidirectional"))
      (node (ref "IC5") (pin "19") (pinfunction "STBY_19") (pintype "bidirectional"))
      (node (ref "IC6") (pin "19") (pinfunction "STBY_19") (pintype "bidirectional"))
    )
    (net (code "54") (name "/TCK") (class "Default")
      (node (ref "IC2") (pin "5") (pinfunction "TCK/SWDCLK_5") (pintype "bidirectional"))
      (node (ref "J5") (pin "5") (pinfunction "5_5") (pintype "bidirectional"))
    )
    (net (code "55") (name "/TDI") (class "Default")
      (node (ref "IC2") (pin "2") (pinfunction "TDI_2") (pintype "bidirectional"))
      (node (ref "J5") (pin "3") (pinfunction "3_3") (pintype "bidirectional"))
    )
    (net (code "56") (name "/TDO") (class "Default")
      (node (ref "IC2") (pin "1") (pinfunction "TDO/SWO_1") (pintype "bidirectional"))
      (node (ref "J5") (pin "7") (pinfunction "7_7") (pintype "bidirectional"))
    )
    (net (code "57") (name "/TMS") (class "Default")
      (node (ref "IC2") (pin "3") (pinfunction "TMS/SWDIO_3") (pintype "bidirectional"))
      (node (ref "J5") (pin "4") (pinfunction "4_4") (pintype "bidirectional"))
    )
    (net (code "58") (name "/TXD0") (class "Default")
      (node (ref "IC2") (pin "98") (pinfunction "P0.2/TXD0/AD0.7_98") (pintype "bidirectional"))
      (node (ref "IC7") (pin "11") (pinfunction "DIN1_11") (pintype "input"))
    )
    (net (code "59") (name "/TXD1") (class "Default")
      (node (ref "IC2") (pin "75") (pinfunction "P2.0/PWM1.1/TXD1/TRACECLK_75") (pintype "bidirectional"))
      (node (ref "IC7") (pin "10") (pinfunction "DIN2_10") (pintype "bidirectional"))
    )
    (net (code "60") (name "/TX_TO_RX") (class "Default")
      (node (ref "IC2") (pin "82") (pinfunction "P4.28/RX_MCLK/MAT2.0/TXD3_82") (pintype "bidirectional"))
      (node (ref "J7") (pin "1") (pinfunction "1_1") (pintype "bidirectional"))
    )
    (net (code "61") (name "/T_RTCK") (class "Default")
      (node (ref "IC2") (pin "57") (pinfunction "P0.21/RI1/CAN_RX1_57") (pintype "bidirectional"))
      (node (ref "J1") (pin "6") (pinfunction "6_6") (pintype "bidirectional"))
      (node (ref "J2") (pin "6") (pinfunction "6_6") (pintype "bidirectional"))
    )
    (net (code "62") (name "/T_SRST") (class "Default")
      (node (ref "IC2") (pin "56") (pinfunction "P0.22/RTS1/CAN_TX1_56") (pintype "bidirectional"))
      (node (ref "J1") (pin "8") (pinfunction "8_8") (pintype "bidirectional"))
      (node (ref "J2") (pin "8") (pinfunction "8_8") (pintype "bidirectional"))
    )
    (net (code "63") (name "/T_SWDCLK") (class "Default")
      (node (ref "IC2") (pin "62") (pinfunction "P0.15/TXD1/SCK0/SCK_62") (pintype "bidirectional"))
      (node (ref "J1") (pin "5") (pinfunction "5_5") (pintype "bidirectional"))
      (node (ref "J2") (pin "5") (pinfunction "5_5") (pintype "bidirectional"))
    )
    (net (code "64") (name "/T_SWDIO") (class "Default")
      (node (ref "IC2") (pin "61") (pinfunction "P0.17/CTS1/MISO0/MISO_61") (pintype "bidirectional"))
      (node (ref "J1") (pin "4") (pinfunction "4_4") (pintype "bidirectional"))
      (node (ref "J2") (pin "4") (pinfunction "4_4") (pintype "bidirectional"))
      (node (ref "R10") (pin "2") (pinfunction "2_2") (pintype "passive"))
    )
    (net (code "65") (name "/T_SWO") (class "Default")
      (node (ref "IC2") (pin "49") (pinfunction "P0.11/RXD2/SCL2/MAT3.1_49") (pintype "bidirectional"))
      (node (ref "J1") (pin "7") (pinfunction "7_7") (pintype "bidirectional"))
      (node (ref "J2") (pin "7") (pinfunction "7_7") (pintype "bidirectional"))
    )
    (net (code "66") (name "/T_TDI") (class "Default")
      (node (ref "IC2") (pin "58") (pinfunction "P0.20/DTR1/SCL1_58") (pintype "bidirectional"))
      (node (ref "J1") (pin "3") (pinfunction "3_3") (pintype "bidirectional"))
      (node (ref "J2") (pin "3") (pinfunction "3_3") (pintype "bidirectional"))
    )
    (net (code "67") (name "/T_TRST") (class "Default")
      (node (ref "IC2") (pin "63") (pinfunction "P0.16/RXD1/SSEL0/SSEL_63") (pintype "bidirectional"))
      (node (ref "J1") (pin "2") (pinfunction "2_2") (pintype "bidirectional"))
      (node (ref "J2") (pin "2") (pinfunction "2_2") (pintype "bidirectional"))
    )
    (net (code "68") (name "GND") (class "Default")
      (node (ref "C1") (pin "1") (pinfunction "1_1") (pintype "passive"))
      (node (ref "C10") (pin "2") (pinfunction "2_2") (pintype "passive"))
      (node (ref "C11") (pin "1") (pinfunction "1_1") (pintype "passive"))
      (node (ref "C12") (pin "1") (pinfunction "1_1") (pintype "passive"))
      (node (ref "C13") (pin "1") (pinfunction "1_1") (pintype "passive"))
      (node (ref "C14") (pin "1") (pinfunction "1_1") (pintype "passive"))
      (node (ref "C15") (pin "1") (pinfunction "1_1") (pintype "passive"))
      (node (ref "C16") (pin "1") (pinfunction "1_1") (pintype "passive"))
      (node (ref "C17") (pin "2") (pinfunction "2_2") (pintype "passive"))
      (node (ref "C18") (pin "1") (pinfunction "1_1") (pintype "passive"))
      (node (ref "C19") (pin "1") (pinfunction "1_1") (pintype "passive"))
      (node (ref "C2") (pin "1") (pinfunction "1_1") (pintype "passive"))
      (node (ref "C20") (pin "1") (pinfunction "1_1") (pintype "passive"))
      (node (ref "C21") (pin "1") (pinfunction "1_1") (pintype "passive"))
      (node (ref "C22") (pin "1") (pinfunction "1_1") (pintype "passive"))
      (node (ref "C23") (pin "2") (pinfunction "2_2") (pintype "passive"))
      (node (ref "C24") (pin "1") (pinfunction "1_1") (pintype "passive"))
      (node (ref "C25") (pin "2") (pinfunction "2_2") (pintype "passive"))
      (node (ref "C26") (pin "2") (pinfunction "2_2") (pintype "passive"))
      (node (ref "C27") (pin "1") (pinfunction "1_1") (pintype "passive"))
      (node (ref "C28") (pin "1") (pinfunction "1_1") (pintype "passive"))
      (node (ref "C29") (pin "1") (pinfunction "1_1") (pintype "passive"))
      (node (ref "C3") (pin "1") (pinfunction "1_1") (pintype "passive"))
      (node (ref "C31") (pin "2") (pinfunction "2_2") (pintype "passive"))
      (node (ref "C33") (pin "1") (pinfunction "1_1") (pintype "passive"))
      (node (ref "C4") (pin "1") (pinfunction "1_1") (pintype "passive"))
      (node (ref "C5") (pin "1") (pinfunction "1_1") (pintype "passive"))
      (node (ref "C6") (pin "2") (pinfunction "2_2") (pintype "passive"))
      (node (ref "C7") (pin "1") (pinfunction "1_1") (pintype "passive"))
      (node (ref "C8") (pin "1") (pinfunction "1_1") (pintype "passive"))
      (node (ref "C9") (pin "2") (pinfunction "2_2") (pintype "passive"))
      (node (ref "CN1") (pin "1") (pinfunction "P$1_1") (pintype "bidirectional"))
      (node (ref "D1") (pin "-") (pinfunction "-_-") (pintype "passive"))
      (node (ref "D2") (pin "-") (pinfunction "-_-") (pintype "passive"))
      (node (ref "D3") (pin "-") (pinfunction "-_-") (pintype "passive"))
      (node (ref "D4") (pin "-") (pinfunction "-_-") (pintype "passive"))
      (node (ref "IC1") (pin "2") (pinfunction "VSS_2") (pintype "bidirectional"))
      (node (ref "IC2") (pin "11") (pinfunction "VSSA_11") (pintype "bidirectional"))
      (node (ref "IC2") (pin "15") (pinfunction "VREFN_15") (pintype "bidirectional"))
      (node (ref "IC2") (pin "16") (pinfunction "RTCX1_16") (pintype "bidirectional"))
      (node (ref "IC2") (pin "31") (pinfunction "VSS_31") (pintype "bidirectional"))
      (node (ref "IC2") (pin "41") (pinfunction "VSS_41") (pintype "bidirectional"))
      (node (ref "IC2") (pin "55") (pinfunction "VSS_55") (pintype "bidirectional"))
      (node (ref "IC2") (pin "72") (pinfunction "VSS_72") (pintype "bidirectional"))
      (node (ref "IC2") (pin "83") (pinfunction "VSS_83") (pintype "bidirectional"))
      (node (ref "IC2") (pin "97") (pinfunction "VSS_97") (pintype "bidirectional"))
      (node (ref "IC3") (pin "1") (pinfunction "GND_1") (pintype "bidirectional"))
      (node (ref "IC4") (pin "2") (pinfunction "VSS_2") (pintype "bidirectional"))
      (node (ref "IC5") (pin "10") (pinfunction "PGND2_10") (pintype "bidirectional"))
      (node (ref "IC5") (pin "18") (pinfunction "GND_18") (pintype "bidirectional"))
      (node (ref "IC5") (pin "3") (pinfunction "PGND_3") (pintype "bidirectional"))
      (node (ref "IC5") (pin "4") (pinfunction "PGND_4") (pintype "bidirectional"))
      (node (ref "IC5") (pin "9") (pinfunction "PGND2_9") (pintype "bidirectional"))
      (node (ref "IC6") (pin "10") (pinfunction "PGND2_10") (pintype "bidirectional"))
      (node (ref "IC6") (pin "18") (pinfunction "GND_18") (pintype "bidirectional"))
      (node (ref "IC6") (pin "3") (pinfunction "PGND_3") (pintype "bidirectional"))
      (node (ref "IC6") (pin "4") (pinfunction "PGND_4") (pintype "bidirectional"))
      (node (ref "IC6") (pin "9") (pinfunction "PGND2_9") (pintype "bidirectional"))
      (node (ref "IC7") (pin "15") (pinfunction "GND_15") (pintype "bidirectional"))
      (node (ref "IR") (pin "3") (pinfunction "GND_3") (pintype "bidirectional"))
      (node (ref "J2") (pin "10") (pinfunction "10_10") (pintype "bidirectional"))
      (node (ref "J2") (pin "11") (pinfunction "11_11") (pintype "bidirectional"))
      (node (ref "J2") (pin "12") (pinfunction "12_12") (pintype "bidirectional"))
      (node (ref "J2") (pin "13") (pinfunction "13_13") (pintype "bidirectional"))
      (node (ref "J2") (pin "14") (pinfunction "14_14") (pintype "bidirectional"))
      (node (ref "J2") (pin "15") (pinfunction "15_15") (pintype "bidirectional"))
      (node (ref "J2") (pin "9") (pinfunction "9_9") (pintype "bidirectional"))
      (node (ref "J3") (pin "5") (pinfunction "GND_5") (pintype "bidirectional"))
      (node (ref "J3") (pin "6") (pinfunction "GND_6") (pintype "bidirectional"))
      (node (ref "J3") (pin "7") (pinfunction "GND_7") (pintype "bidirectional"))
      (node (ref "J4") (pin "3") (pinfunction "3_3") (pintype "bidirectional"))
      (node (ref "J4") (pin "5") (pinfunction "5_5") (pintype "bidirectional"))
      (node (ref "J4") (pin "6") (pinfunction "6_6") (pintype "bidirectional"))
      (node (ref "J4") (pin "G1") (pinfunction "10_G1") (pintype "bidirectional"))
      (node (ref "J4") (pin "G2") (pinfunction "11_G2") (pintype "bidirectional"))
      (node (ref "J5") (pin "10") (pinfunction "10_10") (pintype "bidirectional"))
      (node (ref "J5") (pin "11") (pinfunction "11_11") (pintype "bidirectional"))
      (node (ref "J5") (pin "12") (pinfunction "12_12") (pintype "bidirectional"))
      (node (ref "J5") (pin "13") (pinfunction "13_13") (pintype "bidirectional"))
      (node (ref "J5") (pin "14") (pinfunction "14_14") (pintype "bidirectional"))
      (node (ref "J5") (pin "15") (pinfunction "15_15") (pintype "bidirectional"))
      (node (ref "J5") (pin "9") (pinfunction "9_9") (pintype "bidirectional"))
      (node (ref "J6") (pin "5") (pinfunction "5_5") (pintype "bidirectional"))
      (node (ref "J7") (pin "4") (pinfunction "4_4") (pintype "bidirectional"))
      (node (ref "J8") (pin "16") (pinfunction "16_16") (pintype "bidirectional"))
      (node (ref "J8") (pin "7") (pinfunction "7_7") (pintype "bidirectional"))
      (node (ref "Q2") (pin "2") (pinfunction "S_2") (pintype "passive"))
      (node (ref "SW1") (pin "1") (pinfunction "1_1") (pintype "bidirectional"))
    )
    (net (code "69") (name "Net-(CN1-P$2)") (class "Default")
      (node (ref "CN1") (pin "2") (pinfunction "P$2_2") (pintype "bidirectional"))
      (node (ref "IC2") (pin "6") (pinfunction "P0.26/AD0.3/AOUT/RXD3_6") (pintype "bidirectional"))
    )
    (net (code "70") (name "Net-(CN1-P$3)") (class "Default")
      (node (ref "CN1") (pin "3") (pinfunction "P$3_3") (pintype "bidirectional"))
      (node (ref "IC2") (pin "7") (pinfunction "P0.25/AD0.2/I2SRX_SDA/TXD3_7") (pintype "bidirectional"))
    )
    (net (code "71") (name "Net-(D1-Pad+)") (class "Default")
      (node (ref "D1") (pin "+") (pinfunction "+_+") (pintype "passive"))
      (node (ref "R17") (pin "2") (pinfunction "2_2") (pintype "passive"))
    )
    (net (code "72") (name "Net-(D2-Pad+)") (class "Default")
      (node (ref "D2") (pin "+") (pinfunction "+_+") (pintype "passive"))
      (node (ref "R18") (pin "2") (pinfunction "2_2") (pintype "passive"))
    )
    (net (code "73") (name "Net-(D3-Pad+)") (class "Default")
      (node (ref "D3") (pin "+") (pinfunction "+_+") (pintype "passive"))
      (node (ref "R1") (pin "2") (pinfunction "2_2") (pintype "passive"))
    )
    (net (code "74") (name "Net-(D4-Pad+)") (class "Default")
      (node (ref "D4") (pin "+") (pinfunction "+_+") (pintype "passive"))
      (node (ref "R15") (pin "1") (pinfunction "1_1") (pintype "passive"))
    )
    (net (code "75") (name "Net-(D5-Pad+)") (class "Default")
      (node (ref "D5") (pin "+") (pinfunction "+_+") (pintype "passive"))
      (node (ref "R11") (pin "1") (pinfunction "1_1") (pintype "passive"))
    )
    (net (code "76") (name "Net-(IC2-P0.10{slash}TXD2{slash}SDA2{slash}MAT3.0)") (class "Default")
      (node (ref "IC2") (pin "48") (pinfunction "P0.10/TXD2/SDA2/MAT3.0_48") (pintype "bidirectional"))
      (node (ref "J1") (pin "1") (pinfunction "1_1") (pintype "bidirectional"))
      (node (ref "J2") (pin "1") (pinfunction "1_1") (pintype "bidirectional"))
      (node (ref "J2") (pin "16") (pinfunction "16_16") (pintype "bidirectional"))
    )
    (net (code "77") (name "Net-(IC2-P0.18{slash}DCD1{slash}MOSI0{slash}MOSI1)") (class "Default")
      (node (ref "IC2") (pin "60") (pinfunction "P0.18/DCD1/MOSI0/MOSI1_60") (pintype "bidirectional"))
      (node (ref "R10") (pin "1") (pinfunction "1_1") (pintype "passive"))
    )
    (net (code "78") (name "Net-(IC2-P0.29{slash}USB_D+)") (class "Default")
      (node (ref "C4") (pin "2") (pinfunction "2_2") (pintype "passive"))
      (node (ref "IC2") (pin "29") (pinfunction "P0.29/USB_D+_29") (pintype "bidirectional"))
      (node (ref "R7") (pin "1") (pinfunction "1_1") (pintype "passive"))
    )
    (net (code "79") (name "Net-(IC2-P0.30{slash}USB_D-)") (class "Default")
      (node (ref "C5") (pin "2") (pinfunction "2_2") (pintype "passive"))
      (node (ref "IC2") (pin "30") (pinfunction "P0.30/USB_D-_30") (pintype "bidirectional"))
      (node (ref "R6") (pin "1") (pinfunction "1_1") (pintype "passive"))
    )
    (net (code "80") (name "Net-(IC2-P1.30{slash}VBUS{slash}AD0.4)") (class "Default")
      (node (ref "IC2") (pin "21") (pinfunction "P1.30/VBUS/AD0.4_21") (pintype "bidirectional"))
      (node (ref "R14") (pin "2") (pinfunction "2_2") (pintype "passive"))
    )
    (net (code "81") (name "Net-(IC2-P2.10{slash}EINT0N{slash}NMI)") (class "Default")
      (node (ref "IC2") (pin "53") (pinfunction "P2.10/EINT0N/NMI_53") (pintype "bidirectional"))
      (node (ref "R12") (pin "1") (pinfunction "1_1") (pintype "passive"))
      (node (ref "SW1") (pin "2") (pinfunction "2_2") (pintype "bidirectional"))
    )
    (net (code "82") (name "Net-(IC2-X1)") (class "Default")
      (node (ref "C14") (pin "2") (pinfunction "2_2") (pintype "passive"))
      (node (ref "IC2") (pin "22") (pinfunction "X1_22") (pintype "bidirectional"))
      (node (ref "Y1") (pin "1") (pinfunction "1_1") (pintype "passive"))
    )
    (net (code "83") (name "Net-(IC2-X2)") (class "Default")
      (node (ref "C13") (pin "2") (pinfunction "2_2") (pintype "passive"))
      (node (ref "IC2") (pin "23") (pinfunction "X2_23") (pintype "bidirectional"))
      (node (ref "Y1") (pin "2") (pinfunction "2_2") (pintype "passive"))
    )
    (net (code "84") (name "Net-(IC7-C1+)") (class "Default")
      (node (ref "C32") (pin "1") (pinfunction "1_1") (pintype "passive"))
      (node (ref "IC7") (pin "1") (pinfunction "C1+_1") (pintype "bidirectional"))
    )
    (net (code "85") (name "Net-(IC7-C1-)") (class "Default")
      (node (ref "C32") (pin "2") (pinfunction "2_2") (pintype "passive"))
      (node (ref "IC7") (pin "3") (pinfunction "C1-_3") (pintype "bidirectional"))
    )
    (net (code "86") (name "Net-(IC7-C2+)") (class "Default")
      (node (ref "C30") (pin "2") (pinfunction "2_2") (pintype "passive"))
      (node (ref "IC7") (pin "4") (pinfunction "C2+_4") (pintype "bidirectional"))
    )
    (net (code "87") (name "Net-(IC7-C2-)") (class "Default")
      (node (ref "C30") (pin "1") (pinfunction "1_1") (pintype "passive"))
      (node (ref "IC7") (pin "5") (pinfunction "C2-_5") (pintype "bidirectional"))
    )
    (net (code "88") (name "Net-(IC7-V+)") (class "Default")
      (node (ref "C31") (pin "1") (pinfunction "1_1") (pintype "passive"))
      (node (ref "IC7") (pin "2") (pinfunction "V+_2") (pintype "bidirectional"))
    )
    (net (code "89") (name "Net-(IC7-V-)") (class "Default")
      (node (ref "C29") (pin "2") (pinfunction "2_2") (pintype "passive"))
      (node (ref "IC7") (pin "6") (pinfunction "V-_6") (pintype "bidirectional"))
    )
    (net (code "90") (name "Net-(J3-DM)") (class "Default")
      (node (ref "J3") (pin "2") (pinfunction "DM_2") (pintype "bidirectional"))
      (node (ref "R6") (pin "2") (pinfunction "2_2") (pintype "passive"))
    )
    (net (code "91") (name "Net-(J3-DP)") (class "Default")
      (node (ref "J3") (pin "3") (pinfunction "DP_3") (pintype "bidirectional"))
      (node (ref "R7") (pin "2") (pinfunction "2_2") (pintype "passive"))
      (node (ref "R8") (pin "1") (pinfunction "1_1") (pintype "passive"))
    )
    (net (code "92") (name "Net-(J9-Pad1)") (class "Default")
      (node (ref "J9") (pin "1") (pinfunction "1_1") (pintype "bidirectional"))
      (node (ref "R13") (pin "1") (pinfunction "1_1") (pintype "passive"))
    )
    (net (code "93") (name "Net-(J10-Pad1)") (class "Default")
      (node (ref "J10") (pin "1") (pinfunction "1_1") (pintype "bidirectional"))
      (node (ref "R9") (pin "1") (pinfunction "1_1") (pintype "passive"))
    )
    (net (code "94") (name "Net-(Q1-B)") (class "Default")
      (node (ref "Q1") (pin "1") (pinfunction "B_1") (pintype "passive"))
      (node (ref "R5") (pin "2") (pinfunction "2_2") (pintype "passive"))
    )
    (net (code "95") (name "Net-(Q1-C)") (class "Default")
      (node (ref "Q1") (pin "3") (pinfunction "C_3") (pintype "passive"))
      (node (ref "R8") (pin "2") (pinfunction "2_2") (pintype "passive"))
    )
    (net (code "96") (name "Net-(Q2-D)") (class "Default")
      (node (ref "D5") (pin "-") (pinfunction "-_-") (pintype "passive"))
      (node (ref "Q2") (pin "3") (pinfunction "D_3") (pintype "passive"))
    )
    (net (code "97") (name "VCC") (class "Default")
      (node (ref "C15") (pin "2") (pinfunction "2_2") (pintype "passive"))
      (node (ref "C33") (pin "2") (pinfunction "2_2") (pintype "passive"))
      (node (ref "C6") (pin "1") (pinfunction "1_1") (pintype "passive"))
      (node (ref "C7") (pin "2") (pinfunction "2_2") (pintype "passive"))
      (node (ref "C8") (pin "2") (pinfunction "2_2") (pintype "passive"))
      (node (ref "IC1") (pin "3") (pinfunction "VDD_3") (pintype "bidirectional"))
      (node (ref "IC3") (pin "3") (pinfunction "IN_3") (pintype "bidirectional"))
      (node (ref "IC4") (pin "3") (pinfunction "VDD_3") (pintype "bidirectional"))
      (node (ref "IC7") (pin "16") (pinfunction "VCC_16") (pintype "bidirectional"))
      (node (ref "J3") (pin "1") (pinfunction "VCC_1") (pintype "bidirectional"))
      (node (ref "J8") (pin "6") (pinfunction "6_6") (pintype "bidirectional"))
      (node (ref "R11") (pin "2") (pinfunction "2_2") (pintype "passive"))
      (node (ref "R14") (pin "1") (pinfunction "1_1") (pintype "passive"))
    )
    (net (code "98") (name "VDD") (class "Default")
      (node (ref "C1") (pin "2") (pinfunction "2_2") (pintype "passive"))
      (node (ref "C10") (pin "1") (pinfunction "1_1") (pintype "passive"))
      (node (ref "C11") (pin "2") (pinfunction "2_2") (pintype "passive"))
      (node (ref "C12") (pin "2") (pinfunction "2_2") (pintype "passive"))
      (node (ref "C18") (pin "2") (pinfunction "2_2") (pintype "passive"))
      (node (ref "C19") (pin "2") (pinfunction "2_2") (pintype "passive"))
      (node (ref "C2") (pin "2") (pinfunction "2_2") (pintype "passive"))
      (node (ref "C20") (pin "2") (pinfunction "2_2") (pintype "passive"))
      (node (ref "C21") (pin "2") (pinfunction "2_2") (pintype "passive"))
      (node (ref "C22") (pin "2") (pinfunction "2_2") (pintype "passive"))
      (node (ref "C25") (pin "1") (pinfunction "1_1") (pintype "passive"))
      (node (ref "C26") (pin "1") (pinfunction "1_1") (pintype "passive"))
      (node (ref "C27") (pin "2") (pinfunction "2_2") (pintype "passive"))
      (node (ref "C28") (pin "2") (pinfunction "2_2") (pintype "passive"))
      (node (ref "C3") (pin "2") (pinfunction "2_2") (pintype "passive"))
      (node (ref "C9") (pin "1") (pinfunction "1_1") (pintype "passive"))
      (node (ref "IC2") (pin "10") (pinfunction "VDDA_10") (pintype "bidirectional"))
      (node (ref "IC2") (pin "12") (pinfunction "VREFP_12") (pintype "bidirectional"))
      (node (ref "IC2") (pin "19") (pinfunction "VBAT_19") (pintype "bidirectional"))
      (node (ref "IC2") (pin "28") (pinfunction "VDD3.3V_28") (pintype "bidirectional"))
      (node (ref "IC2") (pin "42") (pinfunction "VDDREG3.3V_42") (pintype "bidirectional"))
      (node (ref "IC2") (pin "54") (pinfunction "VDD3.3V_54") (pintype "bidirectional"))
      (node (ref "IC2") (pin "71") (pinfunction "VDD3.3V_71") (pintype "bidirectional"))
      (node (ref "IC2") (pin "84") (pinfunction "VDDREG3.3V_84") (pintype "bidirectional"))
      (node (ref "IC2") (pin "96") (pinfunction "VDD3.3V_96") (pintype "bidirectional"))
      (node (ref "IC3") (pin "2") (pinfunction "OUT_2") (pintype "bidirectional"))
      (node (ref "IC3") (pin "TER") (pinfunction "OUT_TER") (pintype "bidirectional"))
      (node (ref "IC5") (pin "20") (pinfunction "VCC_20") (pintype "bidirectional"))
      (node (ref "IC6") (pin "20") (pinfunction "VCC_20") (pintype "bidirectional"))
      (node (ref "IR") (pin "2") (pinfunction "VS_2") (pintype "bidirectional"))
      (node (ref "J5") (pin "1") (pinfunction "1_1") (pintype "bidirectional"))
      (node (ref "J5") (pin "16") (pinfunction "16_16") (pintype "bidirectional"))
      (node (ref "J7") (pin "6") (pinfunction "6_6") (pintype "bidirectional"))
      (node (ref "J7") (pin "8") (pinfunction "8_8") (pintype "bidirectional"))
      (node (ref "J8") (pin "10") (pinfunction "10_10") (pintype "bidirectional"))
      (node (ref "Q1") (pin "2") (pinfunction "E_2") (pintype "passive"))
      (node (ref "R12") (pin "2") (pinfunction "2_2") (pintype "passive"))
      (node (ref "R15") (pin "2") (pinfunction "2_2") (pintype "passive"))
      (node (ref "R16") (pin "2") (pinfunction "2_2") (pintype "passive"))
    )
    (net (code "99") (name "unconnected-(IC2-NC-Pad13)") (class "Default")
      (node (ref "IC2") (pin "13") (pinfunction "NC_13") (pintype "bidirectional"))
    )
    (net (code "100") (name "unconnected-(IC2-P0.7{slash}I2STX_CLK{slash}SCK1{slash}MAT2.1-Pad78)") (class "Default")
      (node (ref "IC2") (pin "78") (pinfunction "P0.7/I2STX_CLK/SCK1/MAT2.1_78") (pintype "bidirectional"))
    )
    (net (code "101") (name "unconnected-(IC2-P0.19{slash}DSR1{slash}MCICLK{slash}SDA1-Pad59)") (class "Default")
      (node (ref "IC2") (pin "59") (pinfunction "P0.19/DSR1/MCICLK/SDA1_59") (pintype "bidirectional"))
    )
    (net (code "102") (name "unconnected-(IC2-P0.27{slash}SDA0{slash}USB_SDA-Pad25)") (class "Default")
      (node (ref "IC2") (pin "25") (pinfunction "P0.27/SDA0/USB_SDA_25") (pintype "bidirectional"))
    )
    (net (code "103") (name "unconnected-(IC2-P0.28{slash}SCL0{slash}USB_SCL-Pad24)") (class "Default")
      (node (ref "IC2") (pin "24") (pinfunction "P0.28/SCL0/USB_SCL_24") (pintype "bidirectional"))
    )
    (net (code "104") (name "unconnected-(IC2-P1.15{slash}ENET-RX_CLK-Pad88)") (class "Default")
      (node (ref "IC2") (pin "88") (pinfunction "P1.15/ENET-RX_CLK_88") (pintype "bidirectional"))
    )
    (net (code "105") (name "unconnected-(IC2-P1.16{slash}ENET-MDC-Pad87)") (class "Default")
      (node (ref "IC2") (pin "87") (pinfunction "P1.16/ENET-MDC_87") (pintype "bidirectional"))
    )
    (net (code "106") (name "unconnected-(IC2-P1.17{slash}ENET-MDIO-Pad86)") (class "Default")
      (node (ref "IC2") (pin "86") (pinfunction "P1.17/ENET-MDIO_86") (pintype "bidirectional"))
    )
    (net (code "107") (name "unconnected-(IC2-P1.19{slash}MC0A{slash}USB_PPWR{slash}CAP1.1-Pad33)") (class "Default")
      (node (ref "IC2") (pin "33") (pinfunction "P1.19/MC0A/USB_PPWR/CAP1.1_33") (pintype "bidirectional"))
    )
    (net (code "108") (name "unconnected-(IC2-P1.20{slash}MCFB0{slash}PWM1.2{slash}SCK0-Pad34)") (class "Default")
      (node (ref "IC2") (pin "34") (pinfunction "P1.20/MCFB0/PWM1.2/SCK0_34") (pintype "bidirectional"))
    )
    (net (code "109") (name "unconnected-(IC2-P1.22{slash}MC0B{slash}USB_PWRD{slash}MAT1.0-Pad36)") (class "Default")
      (node (ref "IC2") (pin "36") (pinfunction "P1.22/MC0B/USB_PWRD/MAT1.0_36") (pintype "bidirectional"))
    )
    (net (code "110") (name "unconnected-(IC2-P1.24{slash}MCFB2{slash}PWM1.5{slash}MOSI0-Pad38)") (class "Default")
      (node (ref "IC2") (pin "38") (pinfunction "P1.24/MCFB2/PWM1.5/MOSI0_38") (pintype "bidirectional"))
    )
    (net (code "111") (name "unconnected-(IC2-P1.25{slash}MC1A{slash}MAT1.1-Pad39)") (class "Default")
      (node (ref "IC2") (pin "39") (pinfunction "P1.25/MC1A/MAT1.1_39") (pintype "bidirectional"))
    )
    (net (code "112") (name "unconnected-(IC2-P1.28{slash}MC2A{slash}PCAP1.0{slash}MAT0.0-Pad44)") (class "Default")
      (node (ref "IC2") (pin "44") (pinfunction "P1.28/MC2A/PCAP1.0/MAT0.0_44") (pintype "bidirectional"))
    )
    (net (code "113") (name "unconnected-(IC2-P1.29{slash}MC2B{slash}PCAP1.1{slash}MAT0.1-Pad45)") (class "Default")
      (node (ref "IC2") (pin "45") (pinfunction "P1.29/MC2B/PCAP1.1/MAT0.1_45") (pintype "bidirectional"))
    )
    (net (code "114") (name "unconnected-(IC2-P1.31{slash}SCK1{slash}AD0.5-Pad20)") (class "Default")
      (node (ref "IC2") (pin "20") (pinfunction "P1.31/SCK1/AD0.5_20") (pintype "bidirectional"))
    )
    (net (code "115") (name "unconnected-(IC2-P2.2{slash}PWM1.3{slash}CTS1{slash}TRACEDATA3-Pad73)") (class "Default")
      (node (ref "IC2") (pin "73") (pinfunction "P2.2/PWM1.3/CTS1/TRACEDATA3_73") (pintype "bidirectional"))
    )
    (net (code "116") (name "unconnected-(IC2-P2.11{slash}EINT1N{slash}I2STX_CLK-Pad52)") (class "Default")
      (node (ref "IC2") (pin "52") (pinfunction "P2.11/EINT1N/I2STX_CLK_52") (pintype "bidirectional"))
    )
    (net (code "117") (name "unconnected-(IC2-P2.12{slash}EINT2N{slash}I2STX_WS-Pad51)") (class "Default")
      (node (ref "IC2") (pin "51") (pinfunction "P2.12/EINT2N/I2STX_WS_51") (pintype "bidirectional"))
    )
    (net (code "118") (name "unconnected-(IC2-P2.13{slash}EINT3N{slash}I2STX_SDA-Pad50)") (class "Default")
      (node (ref "IC2") (pin "50") (pinfunction "P2.13/EINT3N/I2STX_SDA_50") (pintype "bidirectional"))
    )
    (net (code "119") (name "unconnected-(IC2-RSTOUTN-Pad14)") (class "Default")
      (node (ref "IC2") (pin "14") (pinfunction "RSTOUTN_14") (pintype "bidirectional"))
    )
    (net (code "120") (name "unconnected-(IC2-RTCX2-Pad18)") (class "Default")
      (node (ref "IC2") (pin "18") (pinfunction "RTCX2_18") (pintype "bidirectional"))
    )
    (net (code "121") (name "unconnected-(J3-ID-Pad4)") (class "Default")
      (node (ref "J3") (pin "4") (pinfunction "ID_4") (pintype "bidirectional"))
    )
    (net (code "122") (name "unconnected-(J4-Pad4)") (class "Default")
      (node (ref "J4") (pin "4") (pinfunction "4_4") (pintype "bidirectional"))
    )
    (net (code "123") (name "unconnected-(J4-Pad9)") (class "Default")
      (node (ref "J4") (pin "9") (pinfunction "9_9") (pintype "bidirectional"))
    )
    (net (code "124") (name "unconnected-(J6-10-PadG1)") (class "Default")
      (node (ref "J6") (pin "G1") (pinfunction "10_G1") (pintype "bidirectional"))
    )
    (net (code "125") (name "unconnected-(J6-11-PadG2)") (class "Default")
      (node (ref "J6") (pin "G2") (pinfunction "11_G2") (pintype "bidirectional"))
    )
    (net (code "126") (name "unconnected-(J6-Pad4)") (class "Default")
      (node (ref "J6") (pin "4") (pinfunction "4_4") (pintype "bidirectional"))
    )
    (net (code "127") (name "unconnected-(J6-Pad7)") (class "Default")
      (node (ref "J6") (pin "7") (pinfunction "7_7") (pintype "bidirectional"))
    )
    (net (code "128") (name "unconnected-(J6-Pad8)") (class "Default")
      (node (ref "J6") (pin "8") (pinfunction "8_8") (pintype "bidirectional"))
    )
    (net (code "129") (name "unconnected-(J6-Pad9)") (class "Default")
      (node (ref "J6") (pin "9") (pinfunction "9_9") (pintype "bidirectional"))
    )
  )
)
